# source_eagle.net
KiCad netlist of a schematic drawn in EAGLE
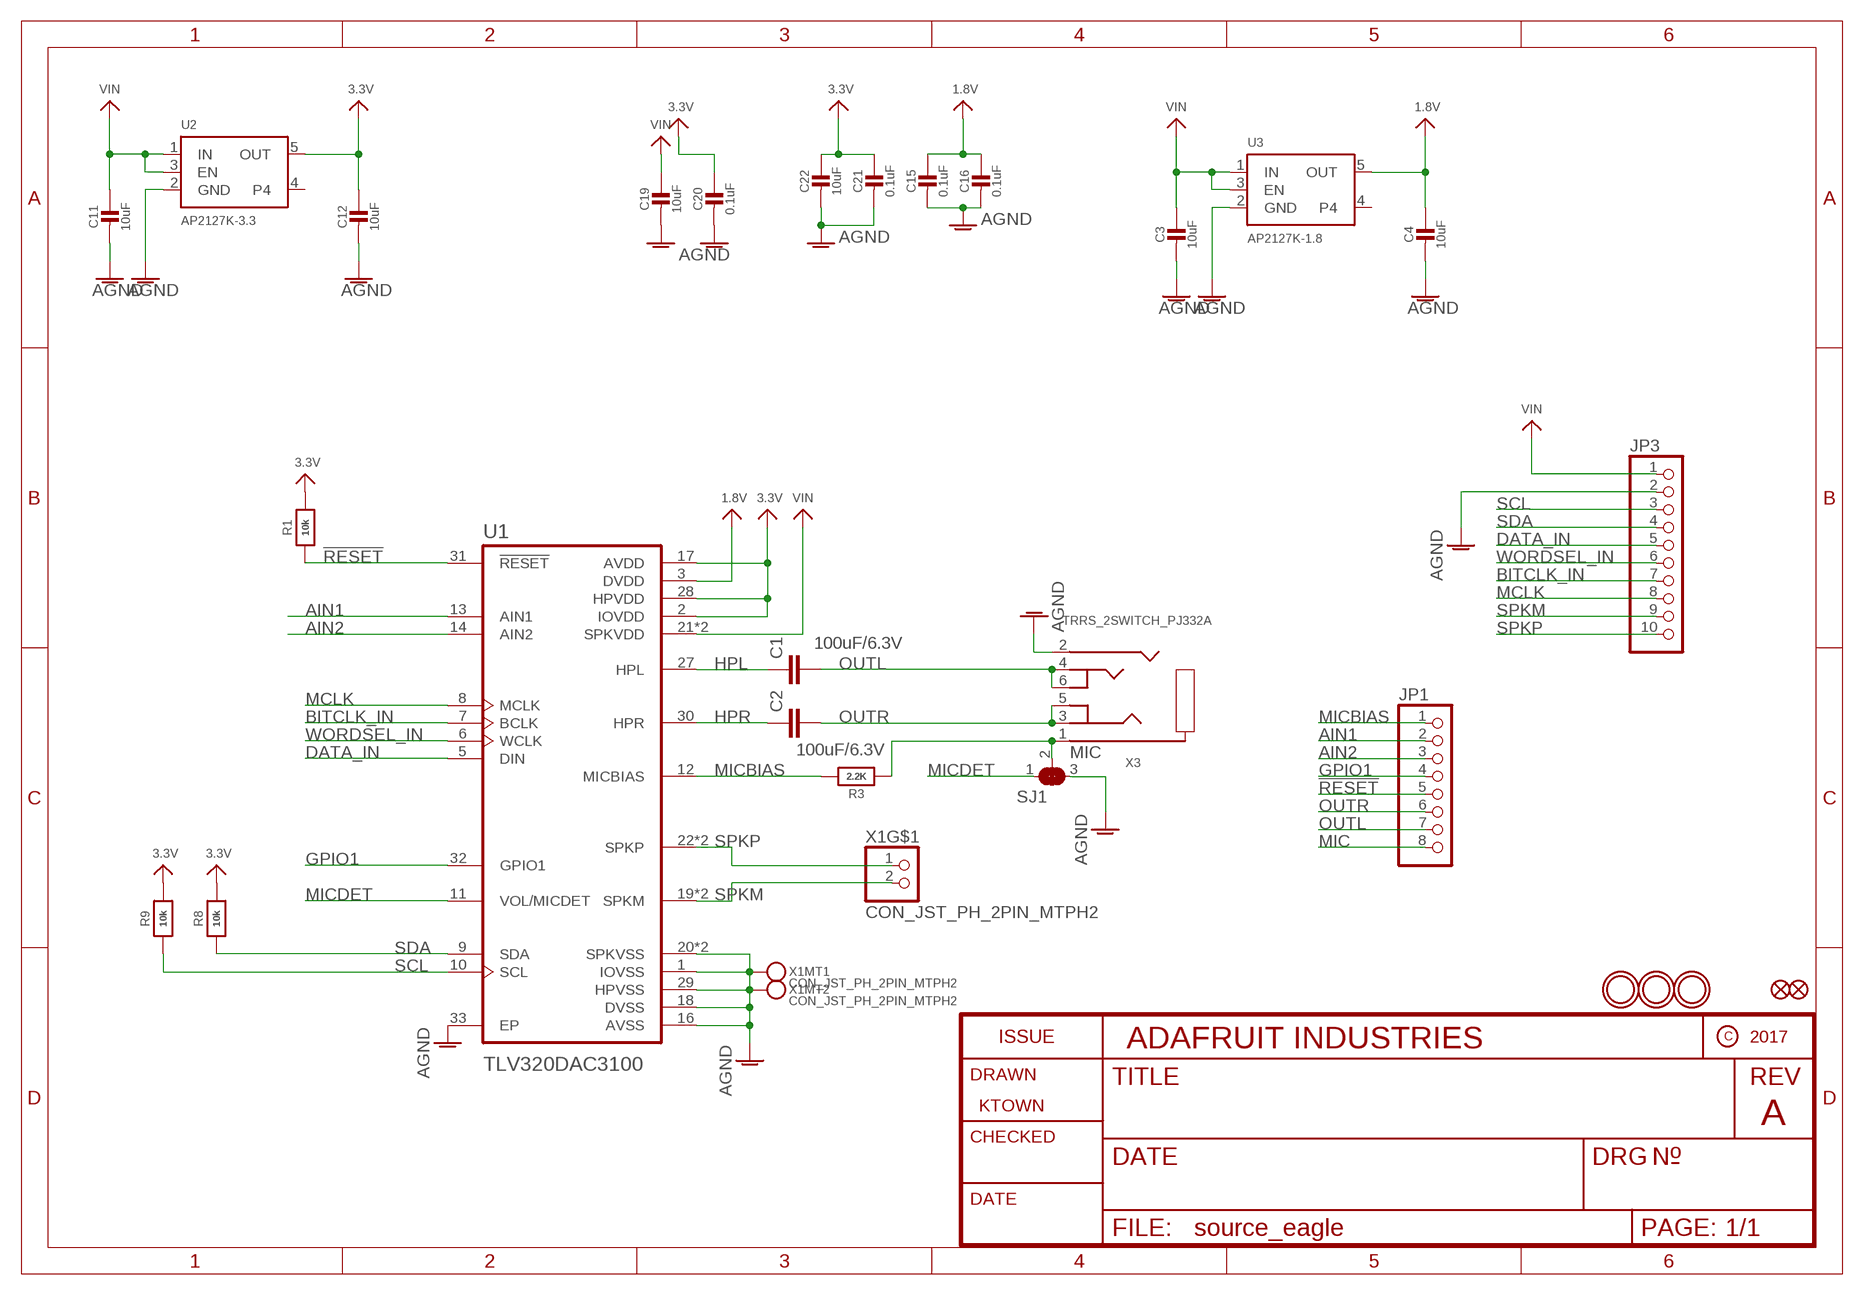
[diagram p0: schematic, sheet 1]

(export (version "E")
  (design (tool "Eeschema 10.0.6"))
  (components
    (comp (ref "C1")
      (value "100uF/6.3V")
      (footprint "eagle-import:C1210")
      (libsource (lib "eagle-import") (part "C-EUC1210"))
    )
    (comp (ref "C2")
      (value "100uF/6.3V")
      (footprint "eagle-import:C1210")
      (libsource (lib "eagle-import") (part "C-EUC1210"))
    )
    (comp (ref "C3")
      (value "10uF")
      (footprint "eagle-import:0805-NO")
      (libsource (lib "eagle-import") (part "CAP_CERAMIC0805-NOOUTLINE"))
    )
    (comp (ref "C4")
      (value "10uF")
      (footprint "eagle-import:0805-NO")
      (libsource (lib "eagle-import") (part "CAP_CERAMIC0805-NOOUTLINE"))
    )
    (comp (ref "C11")
      (value "10uF")
      (footprint "eagle-import:0805-NO")
      (libsource (lib "eagle-import") (part "CAP_CERAMIC0805-NOOUTLINE"))
    )
    (comp (ref "C12")
      (value "10uF")
      (footprint "eagle-import:0805-NO")
      (libsource (lib "eagle-import") (part "CAP_CERAMIC0805-NOOUTLINE"))
    )
    (comp (ref "C15")
      (value "0.1uF")
      (footprint "eagle-import:0603-NO")
      (libsource (lib "eagle-import") (part "CAP_CERAMIC0603_NO"))
    )
    (comp (ref "C16")
      (value "0.1uF")
      (footprint "eagle-import:0603-NO")
      (libsource (lib "eagle-import") (part "CAP_CERAMIC0603_NO"))
    )
    (comp (ref "C19")
      (value "10uF")
      (footprint "eagle-import:0805-NO")
      (libsource (lib "eagle-import") (part "CAP_CERAMIC0805-NOOUTLINE"))
    )
    (comp (ref "C20")
      (value "0.1uF")
      (footprint "eagle-import:0603-NO")
      (libsource (lib "eagle-import") (part "CAP_CERAMIC0603_NO"))
    )
    (comp (ref "C21")
      (value "0.1uF")
      (footprint "eagle-import:0603-NO")
      (libsource (lib "eagle-import") (part "CAP_CERAMIC0603_NO"))
    )
    (comp (ref "C22")
      (value "10uF")
      (footprint "eagle-import:0805-NO")
      (libsource (lib "eagle-import") (part "CAP_CERAMIC0805-NOOUTLINE"))
    )
    (comp (ref "FID1")
      (value "FIDUCIAL_0.5MM")
      (footprint "eagle-import:FIDUCIAL_0.5MM")
      (libsource (lib "eagle-import") (part "FIDUCIAL_0.5MM"))
    )
    (comp (ref "FID2")
      (value "FIDUCIAL_0.5MM")
      (footprint "eagle-import:FIDUCIAL_0.5MM")
      (libsource (lib "eagle-import") (part "FIDUCIAL_0.5MM"))
    )
    (comp (ref "JP1")
      (value "HEADER-1X870MIL")
      (footprint "eagle-import:1X08_ROUND_70")
      (libsource (lib "eagle-import") (part "HEADER-1X870MIL"))
    )
    (comp (ref "JP3")
      (value "HEADER-1X1070MIL")
      (footprint "eagle-import:1X10_ROUND70")
      (libsource (lib "eagle-import") (part "HEADER-1X1070MIL"))
    )
    (comp (ref "R1")
      (value "10k")
      (footprint "eagle-import:0603-NO")
      (libsource (lib "eagle-import") (part "RESISTOR_0603_NOOUT"))
    )
    (comp (ref "R3")
      (value "2.2K")
      (footprint "eagle-import:0603-NO")
      (libsource (lib "eagle-import") (part "RESISTOR_0603_NOOUT"))
    )
    (comp (ref "R8")
      (value "10k")
      (footprint "eagle-import:0603-NO")
      (libsource (lib "eagle-import") (part "RESISTOR_0603_NOOUT"))
    )
    (comp (ref "R9")
      (value "10k")
      (footprint "eagle-import:0603-NO")
      (libsource (lib "eagle-import") (part "RESISTOR_0603_NOOUT"))
    )
    (comp (ref "SJ1")
      (value "SOLDERJUMPER_2WAY")
      (footprint "eagle-import:SOLDERJUMPER_2WAY_OPEN_NOPASTE")
      (libsource (lib "eagle-import") (part "SOLDERJUMPER_2WAY"))
    )
    (comp (ref "U$12")
      (value "MOUNTINGHOLE2.5")
      (footprint "eagle-import:MOUNTINGHOLE_2.5_PLATED")
      (libsource (lib "eagle-import") (part "MOUNTINGHOLE2.5"))
    )
    (comp (ref "U$13")
      (value "MOUNTINGHOLE2.5")
      (footprint "eagle-import:MOUNTINGHOLE_2.5_PLATED")
      (libsource (lib "eagle-import") (part "MOUNTINGHOLE2.5"))
    )
    (comp (ref "U$14")
      (value "MOUNTINGHOLE2.5")
      (footprint "eagle-import:MOUNTINGHOLE_2.5_PLATED")
      (libsource (lib "eagle-import") (part "MOUNTINGHOLE2.5"))
    )
    (comp (ref "U1")
      (value "TLV320DAC3100")
      (footprint "eagle-import:TLV320DAC3100")
      (libsource (lib "eagle-import") (part "TLV320DAC3100"))
    )
    (comp (ref "U2")
      (value "AP2127K-3.3")
      (footprint "eagle-import:SOT23-5")
      (libsource (lib "eagle-import") (part "VREG_SOT23-5"))
    )
    (comp (ref "U3")
      (value "AP2127K-1.8")
      (footprint "eagle-import:SOT23-5")
      (libsource (lib "eagle-import") (part "VREG_SOT23-5"))
    )
    (comp (ref "X1")
      (value "CON_JST_PH_2PIN_MTPH2")
      (footprint "eagle-import:JSTPH2")
      (libsource (lib "eagle-import") (part "CON_JST_PH_2PIN_MTPH2"))
    )
    (comp (ref "X3")
      (value "TRRS_2SWITCH_PJ332A")
      (footprint "eagle-import:PJ-332A")
      (libsource (lib "eagle-import") (part "TRRS_2SWITCH_PJ332A"))
    )
  )
  (nets
    (net (code "1") (name "/AIN1") (class "Default")
      (node (ref "JP1") (pin "2") (pinfunction "2_2") (pintype "passive"))
      (node (ref "U1") (pin "13") (pinfunction "AIN1_13") (pintype "input"))
    )
    (net (code "2") (name "/AIN2") (class "Default")
      (node (ref "JP1") (pin "3") (pinfunction "3_3") (pintype "passive"))
      (node (ref "U1") (pin "14") (pinfunction "AIN2_14") (pintype "input"))
    )
    (net (code "3") (name "/BITCLK_IN") (class "Default")
      (node (ref "JP3") (pin "7") (pinfunction "7_7") (pintype "passive"))
      (node (ref "U1") (pin "7") (pinfunction "BCLK_7") (pintype "input"))
    )
    (net (code "4") (name "/DATA_IN") (class "Default")
      (node (ref "JP3") (pin "5") (pinfunction "5_5") (pintype "passive"))
      (node (ref "U1") (pin "5") (pinfunction "DIN_5") (pintype "input"))
    )
    (net (code "5") (name "/GPIO1") (class "Default")
      (node (ref "JP1") (pin "4") (pinfunction "4_4") (pintype "passive"))
      (node (ref "U1") (pin "32") (pinfunction "GPIO1_32") (pintype "bidirectional"))
    )
    (net (code "6") (name "/HPL") (class "Default")
      (node (ref "C1") (pin "1") (pinfunction "1_1") (pintype "passive"))
      (node (ref "U1") (pin "27") (pinfunction "HPL_27") (pintype "output"))
    )
    (net (code "7") (name "/HPR") (class "Default")
      (node (ref "C2") (pin "1") (pinfunction "1_1") (pintype "passive"))
      (node (ref "U1") (pin "30") (pinfunction "HPR_30") (pintype "output"))
    )
    (net (code "8") (name "/MCLK") (class "Default")
      (node (ref "JP3") (pin "8") (pinfunction "8_8") (pintype "passive"))
      (node (ref "U1") (pin "8") (pinfunction "MCLK_8") (pintype "input"))
    )
    (net (code "9") (name "/MIC") (class "Default")
      (node (ref "JP1") (pin "8") (pinfunction "8_8") (pintype "passive"))
      (node (ref "R3") (pin "1") (pinfunction "1_1") (pintype "passive"))
      (node (ref "SJ1") (pin "2") (pinfunction "2_2") (pintype "passive"))
      (node (ref "X3") (pin "1") (pinfunction "RING_1") (pintype "passive"))
    )
    (net (code "10") (name "/MICBIAS") (class "Default")
      (node (ref "JP1") (pin "1") (pinfunction "1_1") (pintype "passive"))
      (node (ref "R3") (pin "2") (pinfunction "2_2") (pintype "passive"))
      (node (ref "U1") (pin "12") (pinfunction "MICBIAS_12") (pintype "output"))
    )
    (net (code "11") (name "/MICDET") (class "Default")
      (node (ref "SJ1") (pin "1") (pinfunction "1_1") (pintype "passive"))
      (node (ref "U1") (pin "11") (pinfunction "VOL/MICDET_11") (pintype "input"))
    )
    (net (code "12") (name "/OUTL") (class "Default")
      (node (ref "C1") (pin "2") (pinfunction "2_2") (pintype "passive"))
      (node (ref "JP1") (pin "7") (pinfunction "7_7") (pintype "passive"))
      (node (ref "X3") (pin "4") (pinfunction "TIP_4") (pintype "passive"))
      (node (ref "X3") (pin "6") (pinfunction "TIP_SW_6") (pintype "passive"))
    )
    (net (code "13") (name "/OUTR") (class "Default")
      (node (ref "C2") (pin "2") (pinfunction "2_2") (pintype "passive"))
      (node (ref "JP1") (pin "6") (pinfunction "6_6") (pintype "passive"))
      (node (ref "X3") (pin "3") (pinfunction "RING2_3") (pintype "passive"))
      (node (ref "X3") (pin "5") (pinfunction "R2_SW_5") (pintype "passive"))
    )
    (net (code "14") (name "/SCL") (class "Default")
      (node (ref "JP3") (pin "3") (pinfunction "3_3") (pintype "passive"))
      (node (ref "R9") (pin "1") (pinfunction "1_1") (pintype "passive"))
      (node (ref "U1") (pin "10") (pinfunction "SCL_10") (pintype "input"))
    )
    (net (code "15") (name "/SDA") (class "Default")
      (node (ref "JP3") (pin "4") (pinfunction "4_4") (pintype "passive"))
      (node (ref "R8") (pin "1") (pinfunction "1_1") (pintype "passive"))
      (node (ref "U1") (pin "9") (pinfunction "SDA_9") (pintype "bidirectional"))
    )
    (net (code "16") (name "/SPKM") (class "Default")
      (node (ref "JP3") (pin "9") (pinfunction "9_9") (pintype "passive"))
      (node (ref "U1") (pin "19") (pinfunction "SPKM_19") (pintype "output"))
      (node (ref "U1") (pin "23") (pinfunction "SPKM_23") (pintype "output"))
      (node (ref "X1") (pin "2") (pinfunction "2_2") (pintype "passive"))
    )
    (net (code "17") (name "/SPKP") (class "Default")
      (node (ref "JP3") (pin "10") (pinfunction "10_10") (pintype "passive"))
      (node (ref "U1") (pin "22") (pinfunction "SPKP_22") (pintype "output"))
      (node (ref "U1") (pin "26") (pinfunction "SPKP_26") (pintype "output"))
      (node (ref "X1") (pin "1") (pinfunction "1_1") (pintype "passive"))
    )
    (net (code "18") (name "/WORDSEL_IN") (class "Default")
      (node (ref "JP3") (pin "6") (pinfunction "6_6") (pintype "passive"))
      (node (ref "U1") (pin "6") (pinfunction "WCLK_6") (pintype "input"))
    )
    (net (code "19") (name "/~{RESET}") (class "Default")
      (node (ref "JP1") (pin "5") (pinfunction "5_5") (pintype "passive"))
      (node (ref "R1") (pin "1") (pinfunction "1_1") (pintype "passive"))
      (node (ref "U1") (pin "31") (pinfunction "~{RESET}_31") (pintype "input"))
    )
    (net (code "20") (name "1.8V") (class "Default")
      (node (ref "C15") (pin "1") (pinfunction "1_1") (pintype "passive"))
      (node (ref "C16") (pin "1") (pinfunction "1_1") (pintype "passive"))
      (node (ref "C4") (pin "1") (pinfunction "1_1") (pintype "passive"))
      (node (ref "U1") (pin "3") (pinfunction "DVDD_3") (pintype "power_in"))
      (node (ref "U3") (pin "5") (pinfunction "OUT_5") (pintype "power_in"))
    )
    (net (code "21") (name "3.3V") (class "Default")
      (node (ref "C12") (pin "1") (pinfunction "1_1") (pintype "passive"))
      (node (ref "C20") (pin "1") (pinfunction "1_1") (pintype "passive"))
      (node (ref "C21") (pin "1") (pinfunction "1_1") (pintype "passive"))
      (node (ref "C22") (pin "1") (pinfunction "1_1") (pintype "passive"))
      (node (ref "R1") (pin "2") (pinfunction "2_2") (pintype "passive"))
      (node (ref "R8") (pin "2") (pinfunction "2_2") (pintype "passive"))
      (node (ref "R9") (pin "2") (pinfunction "2_2") (pintype "passive"))
      (node (ref "U1") (pin "17") (pinfunction "AVDD_17") (pintype "power_in"))
      (node (ref "U1") (pin "2") (pinfunction "IOVDD_2") (pintype "power_in"))
      (node (ref "U1") (pin "28") (pinfunction "HPVDD_28") (pintype "power_in"))
      (node (ref "U2") (pin "5") (pinfunction "OUT_5") (pintype "power_in"))
    )
    (net (code "22") (name "AGND") (class "Default")
      (node (ref "C11") (pin "2") (pinfunction "2_2") (pintype "passive"))
      (node (ref "C12") (pin "2") (pinfunction "2_2") (pintype "passive"))
      (node (ref "C15") (pin "2") (pinfunction "2_2") (pintype "passive"))
      (node (ref "C16") (pin "2") (pinfunction "2_2") (pintype "passive"))
      (node (ref "C19") (pin "2") (pinfunction "2_2") (pintype "passive"))
      (node (ref "C20") (pin "2") (pinfunction "2_2") (pintype "passive"))
      (node (ref "C21") (pin "2") (pinfunction "2_2") (pintype "passive"))
      (node (ref "C22") (pin "2") (pinfunction "2_2") (pintype "passive"))
      (node (ref "C3") (pin "2") (pinfunction "2_2") (pintype "passive"))
      (node (ref "C4") (pin "2") (pinfunction "2_2") (pintype "passive"))
      (node (ref "JP3") (pin "2") (pinfunction "2_2") (pintype "passive"))
      (node (ref "SJ1") (pin "3") (pinfunction "3_3") (pintype "passive"))
      (node (ref "U1") (pin "1") (pinfunction "IOVSS_1") (pintype "power_in"))
      (node (ref "U1") (pin "16") (pinfunction "AVSS_16") (pintype "power_in"))
      (node (ref "U1") (pin "18") (pinfunction "DVSS_18") (pintype "power_in"))
      (node (ref "U1") (pin "20") (pinfunction "SPKVSS_20") (pintype "power_in"))
      (node (ref "U1") (pin "25") (pinfunction "SPKVSS_25") (pintype "power_in"))
      (node (ref "U1") (pin "29") (pinfunction "HPVSS_29") (pintype "power_in"))
      (node (ref "U1") (pin "33") (pinfunction "EP_33") (pintype "bidirectional"))
      (node (ref "U2") (pin "2") (pinfunction "GND_2") (pintype "power_in"))
      (node (ref "U3") (pin "2") (pinfunction "GND_2") (pintype "power_in"))
      (node (ref "X1") (pin "NC1") (pinfunction "P$1_NC1") (pintype "bidirectional"))
      (node (ref "X1") (pin "NC2") (pinfunction "P$1_NC2") (pintype "bidirectional"))
      (node (ref "X3") (pin "2") (pinfunction "RING1_2") (pintype "passive"))
    )
    (net (code "23") (name "VIN") (class "Default")
      (node (ref "C11") (pin "1") (pinfunction "1_1") (pintype "passive"))
      (node (ref "C19") (pin "1") (pinfunction "1_1") (pintype "passive"))
      (node (ref "C3") (pin "1") (pinfunction "1_1") (pintype "passive"))
      (node (ref "JP3") (pin "1") (pinfunction "1_1") (pintype "passive"))
      (node (ref "U1") (pin "21") (pinfunction "SPKVDD_21") (pintype "power_in"))
      (node (ref "U1") (pin "24") (pinfunction "SPKVDD_24") (pintype "power_in"))
      (node (ref "U2") (pin "1") (pinfunction "IN_1") (pintype "power_in"))
      (node (ref "U2") (pin "3") (pinfunction "EN_3") (pintype "input"))
      (node (ref "U3") (pin "1") (pinfunction "IN_1") (pintype "power_in"))
      (node (ref "U3") (pin "3") (pinfunction "EN_3") (pintype "input"))
    )
    (net (code "24") (name "unconnected-(U2-P4-Pad4)") (class "Default")
      (node (ref "U2") (pin "4") (pinfunction "P4_4") (pintype "bidirectional"))
    )
    (net (code "25") (name "unconnected-(U3-P4-Pad4)") (class "Default")
      (node (ref "U3") (pin "4") (pinfunction "P4_4") (pintype "bidirectional"))
    )
  )
)
